# ExampleCircuit.net
KiCad netlist of a schematic drawn in Altium Designer
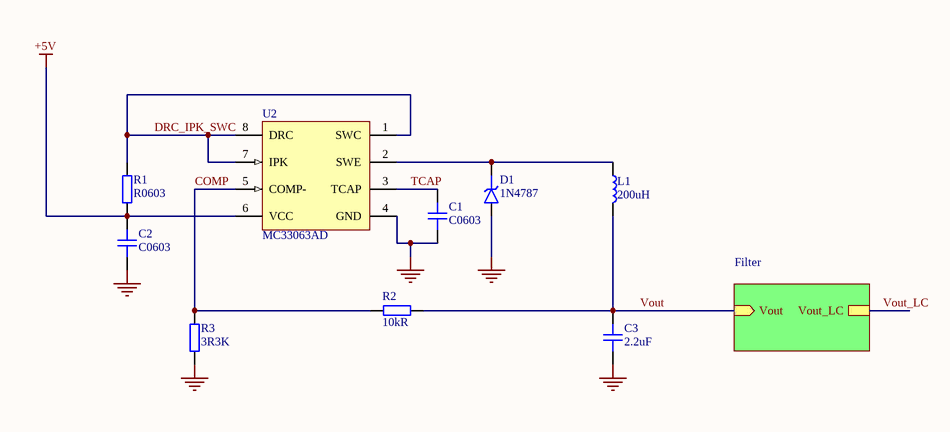
[diagram p0: ExampleCircuit.SchDoc]

(export (version "E")
  (design (tool "Eeschema 10.0.6"))
  (components
    (comp (ref "C1")
      (value "C0603")
      (footprint "CAP_0603")
      (description "Capacitor SMD 0603")
      (libsource (lib "PhilsLabLib.") (part "CAP_0603"))
    )
    (comp (ref "C2")
      (value "C0603")
      (footprint "CAP_0603")
      (description "Capacitor SMD 0603")
      (libsource (lib "PhilsLabLib.") (part "CAP_0603"))
    )
    (comp (ref "C3")
      (value "2.2uF")
      (footprint "CAP_0603")
      (description "Capacitor SMD 0603")
      (libsource (lib "PhilsLabLib.") (part "CAP_0603"))
    )
    (comp (ref "D1")
      (value "1N4787")
      (footprint "SOD-323")
      (description "Diode Zener SMD SOD-323")
      (libsource (lib "PhilsLabLib.") (part "D_ZENER_SOD_323"))
    )
    (comp (ref "L1")
      (value "200uH")
      (footprint "IND_0603")
      (description "Inductor SMD 0603")
      (libsource (lib "PhilsLabLib.") (part "IND_0603"))
    )
    (comp (ref "R1")
      (value "R0603")
      (footprint "RES_0603")
      (description "Resistor SMD 0603")
      (libsource (lib "PhilsLabLib.") (part "RES_0603"))
    )
    (comp (ref "R2")
      (value "10kR")
      (footprint "RES_0603")
      (description "Resistor SMD 0603")
      (libsource (lib "PhilsLabLib.") (part "RES_0603"))
    )
    (comp (ref "R3")
      (value "3R3K")
      (footprint "RES_0603")
      (description "Resistor SMD 0603")
      (libsource (lib "PhilsLabLib.") (part "RES_0603"))
    )
    (comp (ref "U2")
      (value "MC33063AD")
      (footprint "D0008A_N")
      (fields (field (name "MANUFACTURER") "Texas Instruments"))
      (libsource (lib "Altium Content Vault") (part "TI-MC33063AD8"))
    )
  )
  (nets
    (net (code "1") (name "+5V") (class "Default")
      (node (ref "C2") (pin "2") (pinfunction "2_2") (pintype "passive"))
      (node (ref "R1") (pin "2") (pinfunction "2_2") (pintype "passive"))
      (node (ref "U2") (pin "6") (pinfunction "VCC_6") (pintype "power_in"))
    )
    (net (code "2") (name "/COMP") (class "Default")
      (node (ref "R2") (pin "2") (pinfunction "2_2") (pintype "passive"))
      (node (ref "R3") (pin "1") (pinfunction "1_1") (pintype "passive"))
      (node (ref "U2") (pin "5") (pinfunction "COMP-_5") (pintype "input"))
    )
    (net (code "3") (name "/DRC_IPK_SWC") (class "Default")
      (node (ref "R1") (pin "1") (pinfunction "1_1") (pintype "passive"))
      (node (ref "U2") (pin "1") (pinfunction "SWC_1") (pintype "open_collector"))
      (node (ref "U2") (pin "7") (pinfunction "IPK_7") (pintype "input"))
      (node (ref "U2") (pin "8") (pinfunction "DRC_8") (pintype "open_collector"))
    )
    (net (code "4") (name "/TCAP") (class "Default")
      (node (ref "C1") (pin "2") (pinfunction "2_2") (pintype "passive"))
      (node (ref "U2") (pin "3") (pinfunction "TCAP_3") (pintype "passive"))
    )
    (net (code "5") (name "/Vout") (class "Default")
      (node (ref "C3") (pin "1") (pinfunction "1_1") (pintype "passive"))
      (node (ref "L1") (pin "2") (pinfunction "2_2") (pintype "passive"))
      (node (ref "R2") (pin "1") (pinfunction "1_1") (pintype "passive"))
    )
    (net (code "7") (name "GND") (class "Default")
      (node (ref "C1") (pin "1") (pinfunction "1_1") (pintype "passive"))
      (node (ref "C2") (pin "1") (pinfunction "1_1") (pintype "passive"))
      (node (ref "C3") (pin "2") (pinfunction "2_2") (pintype "passive"))
      (node (ref "D1") (pin "A") (pinfunction "A_A") (pintype "passive"))
      (node (ref "R3") (pin "2") (pinfunction "2_2") (pintype "passive"))
      (node (ref "U2") (pin "4") (pinfunction "GND_4") (pintype "power_in"))
    )
    (net (code "8") (name "Net-(U2-SWE)") (class "Default")
      (node (ref "D1") (pin "K") (pinfunction "K_K") (pintype "passive"))
      (node (ref "L1") (pin "1") (pinfunction "1_1") (pintype "passive"))
      (node (ref "U2") (pin "2") (pinfunction "SWE_2") (pintype "open_emitter"))
    )
  )
)
